# Sheet1.net
KiCad netlist of a schematic drawn in Altium Designer
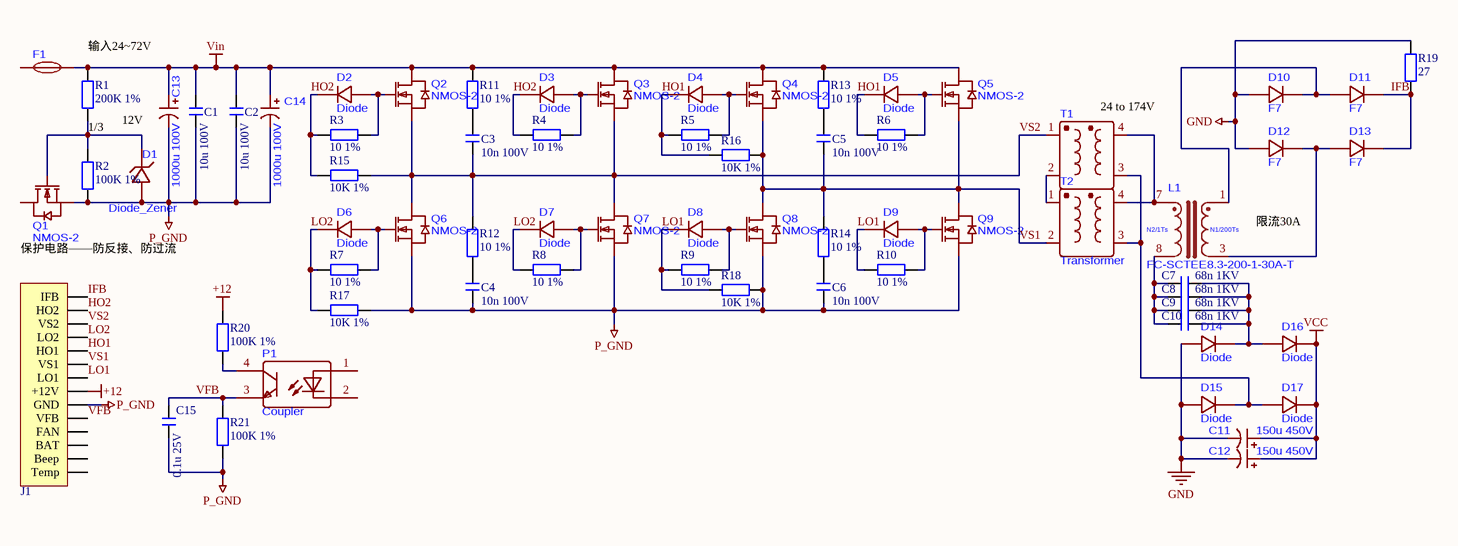
[diagram p0: Sheet1.SchDoc]

(export (version "E")
  (design (tool "Eeschema 10.0.6"))
  (components
    (comp (ref "C1")
      (value "10u 100V")
      (footprint "C2220")
      (description "贴片电容")
      (libsource (lib "自建库") (part "CAP"))
    )
    (comp (ref "C2")
      (value "10u 100V")
      (footprint "C2220")
      (description "贴片电容")
      (libsource (lib "自建库") (part "CAP"))
    )
    (comp (ref "C3")
      (value "10n 100V")
      (footprint "C2220")
      (description "贴片电容")
      (libsource (lib "自建库") (part "CAP"))
    )
    (comp (ref "C4")
      (value "10n 100V")
      (footprint "C2220")
      (description "贴片电容")
      (libsource (lib "自建库") (part "CAP"))
    )
    (comp (ref "C5")
      (value "10n 100V")
      (footprint "C2220")
      (description "贴片电容")
      (libsource (lib "自建库") (part "CAP"))
    )
    (comp (ref "C6")
      (value "10n 100V")
      (footprint "C2220")
      (description "贴片电容")
      (libsource (lib "自建库") (part "CAP"))
    )
    (comp (ref "C7")
      (value "68n 1KV")
      (footprint "CAP-TH_L18.0-W8.5-P15.00-D0.8")
      (description "贴片电容/安规电容")
      (fields (field (name "PART_NUMBER") "MMK683J3ADSAJ208G0"))
      (libsource (lib "自建库") (part "CAP"))
    )
    (comp (ref "C8")
      (value "68n 1KV")
      (footprint "CAP-TH_L18.0-W8.5-P15.00-D0.8")
      (description "贴片电容/安规电容")
      (fields (field (name "PART_NUMBER") "MMK683J3ADSAJ208G0"))
      (libsource (lib "自建库") (part "CAP"))
    )
    (comp (ref "C9")
      (value "68n 1KV")
      (footprint "CAP-TH_L18.0-W8.5-P15.00-D0.8")
      (description "贴片电容/安规电容")
      (fields (field (name "PART_NUMBER") "MMK683J3ADSAJ208G0"))
      (libsource (lib "自建库") (part "CAP"))
    )
    (comp (ref "C10")
      (value "68n 1KV")
      (footprint "CAP-TH_L18.0-W8.5-P15.00-D0.8")
      (description "贴片电容/安规电容")
      (fields (field (name "PART_NUMBER") "MMK683J3ADSAJ208G0"))
      (libsource (lib "自建库") (part "CAP"))
    )
    (comp (ref "C11")
      (value "150u 450V")
      (footprint "CAP-TH_BD22.0-P10.00-D2.3-FD")
      (description "固态电容/电解电容")
      (fields (field (name "PART_NUMBER") "KN151M45022*35A"))
      (libsource (lib "自建库") (part "CAP_1"))
    )
    (comp (ref "C12")
      (value "150u 450V")
      (footprint "CAP-TH_BD22.0-P10.00-D2.3-FD")
      (description "固态电容/电解电容")
      (fields (field (name "PART_NUMBER") "KN151M45022*35A"))
      (libsource (lib "自建库") (part "CAP_1"))
    )
    (comp (ref "C13")
      (value "1000u 100V")
      (footprint "CAP-TH_BD18.0-P7.50-D0.8-FD")
      (description "固态电容/电解电容")
      (fields (field (name "PART_NUMBER") "KF102M10018*36A"))
      (libsource (lib "自建库") (part "CAP_1"))
    )
    (comp (ref "C14")
      (value "1000u 100V")
      (footprint "CAP-TH_BD22.0-P10.00-D2.3-FD")
      (description "固态电容/电解电容")
      (fields (field (name "PART_NUMBER") "KF102M10018*36A"))
      (libsource (lib "自建库") (part "CAP_1"))
    )
    (comp (ref "C15")
      (value "0.1u 25V")
      (footprint "C0805")
      (description "贴片电容/安规电容")
      (fields (field (name "PART_NUMBER") "CC0805MRX7R8BB104"))
      (libsource (lib "自建库") (part "CAP"))
    )
    (comp (ref "D1")
      (value "Diode_Zener")
      (footprint "SOD-123_L2.7-W1.6-LS3.7-RD-1")
      (description "稳压二极管（齐纳二极管），12V,500mW")
      (fields (field (name "PART_NUMBER") "BZT52C12"))
      (libsource (lib "自建库") (part "Diode_Zener"))
    )
    (comp (ref "D2")
      (value "Diode")
      (footprint "SOD-123_L2.7-W1.6-LS3.7-RD-1")
      (description "Diode,1N4148W,开关二极管,CJ(江苏长电/长晶)")
      (fields (field (name "PART_NUMBER") "1N4148W"))
      (libsource (lib "自建库") (part "Diode"))
    )
    (comp (ref "D3")
      (value "Diode")
      (footprint "SOD-123_L2.7-W1.6-LS3.7-RD-1")
      (description "Diode,1N4148W,开关二极管,CJ(江苏长电/长晶)")
      (fields (field (name "PART_NUMBER") "1N4148W"))
      (libsource (lib "自建库") (part "Diode"))
    )
    (comp (ref "D4")
      (value "Diode")
      (footprint "SOD-123_L2.7-W1.6-LS3.7-RD-1")
      (description "Diode,1N4148W,开关二极管,CJ(江苏长电/长晶)")
      (fields (field (name "PART_NUMBER") "1N4148W"))
      (libsource (lib "自建库") (part "Diode"))
    )
    (comp (ref "D5")
      (value "Diode")
      (footprint "SOD-123_L2.7-W1.6-LS3.7-RD-1")
      (description "Diode,1N4148W,开关二极管,CJ(江苏长电/长晶)")
      (fields (field (name "PART_NUMBER") "1N4148W"))
      (libsource (lib "自建库") (part "Diode"))
    )
    (comp (ref "D6")
      (value "Diode")
      (footprint "SOD-123_L2.7-W1.6-LS3.7-RD-1")
      (description "Diode,1N4148W,开关二极管,CJ(江苏长电/长晶)")
      (fields (field (name "PART_NUMBER") "1N4148W"))
      (libsource (lib "自建库") (part "Diode"))
    )
    (comp (ref "D7")
      (value "Diode")
      (footprint "SOD-123_L2.7-W1.6-LS3.7-RD-1")
      (description "Diode,1N4148W,开关二极管,CJ(江苏长电/长晶)")
      (fields (field (name "PART_NUMBER") "1N4148W"))
      (libsource (lib "自建库") (part "Diode"))
    )
    (comp (ref "D8")
      (value "Diode")
      (footprint "SOD-123_L2.7-W1.6-LS3.7-RD-1")
      (description "Diode,1N4148W,开关二极管,CJ(江苏长电/长晶)")
      (fields (field (name "PART_NUMBER") "1N4148W"))
      (libsource (lib "自建库") (part "Diode"))
    )
    (comp (ref "D9")
      (value "Diode")
      (footprint "SOD-123_L2.7-W1.6-LS3.7-RD-1")
      (description "Diode,1N4148W,开关二极管,CJ(江苏长电/长晶)")
      (fields (field (name "PART_NUMBER") "1N4148W"))
      (libsource (lib "自建库") (part "Diode"))
    )
    (comp (ref "D10")
      (value "F7")
      (footprint "DO-214AC_L4.3-W2.7-LS5.2-RD")
      (description "Diode，快恢复/超快恢复二极管，1KV，1A")
      (libsource (lib "自建库") (part "Diode"))
    )
    (comp (ref "D11")
      (value "F7")
      (footprint "DO-214AC_L4.3-W2.7-LS5.2-RD")
      (description "Diode，快恢复/超快恢复二极管，1KV，1A")
      (libsource (lib "自建库") (part "Diode"))
    )
    (comp (ref "D12")
      (value "F7")
      (footprint "DO-214AC_L4.3-W2.7-LS5.2-RD")
      (description "Diode，快恢复/超快恢复二极管，1KV，1A")
      (libsource (lib "自建库") (part "Diode"))
    )
    (comp (ref "D13")
      (value "F7")
      (footprint "DO-214AC_L4.3-W2.7-LS5.2-RD")
      (description "Diode，快恢复/超快恢复二极管，1KV，1A")
      (libsource (lib "自建库") (part "Diode"))
    )
    (comp (ref "D14")
      (value "Diode")
      (footprint "DO-214AC_L4.3-W2.7-LS5.2-RD")
      (fields (field (name "PART_NUMBER") "GC6D10065A"))
      (libsource (lib "自建库") (part "Diode"))
    )
    (comp (ref "D15")
      (value "Diode")
      (footprint "DO-214AC_L4.3-W2.7-LS5.2-RD")
      (fields (field (name "PART_NUMBER") "GC6D10065A"))
      (libsource (lib "自建库") (part "Diode"))
    )
    (comp (ref "D16")
      (value "Diode")
      (footprint "DO-214AC_L4.3-W2.7-LS5.2-RD")
      (fields (field (name "PART_NUMBER") "GC6D10065A"))
      (libsource (lib "自建库") (part "Diode"))
    )
    (comp (ref "D17")
      (value "Diode")
      (footprint "DO-214AC_L4.3-W2.7-LS5.2-RD")
      (fields (field (name "PART_NUMBER") "GC6D10065A"))
      (libsource (lib "自建库") (part "Diode"))
    )
    (comp (ref "F1")
      (value "Fuse-S1032-F-50.0A")
      (footprint "FUSE-SMD_L10.3-W3.2")
      (description "一次性保险丝，额定50A，分断180A")
      (fields (field (name "PART_NUMBER") "S1032-F-50.0A"))
      (libsource (lib "自建库") (part "Fuse-S1032-F-50.0A"))
    )
    (comp (ref "J1")
      (value "HDR-1X14")
      (footprint "HDR2.54-Y-LI-14P")
      (description "Header, 14-Pin")
      (libsource (lib "自建库") (part "EGT003"))
    )
    (comp (ref "L1")
      (value "FC-SCTEE8.3-200-1-30A-T")
      (footprint "XFMR-SMD_FC-SCTEE8.3-200-1-30A-T")
      (description "交流互感器,30A,1:200")
      (libsource (lib "自建库") (part "FC-SCTEE8.3-200-1-30A-T"))
    )
    (comp (ref "P1")
      (value "Coupler")
      (footprint "SOP-4_L6.5-W4.6-P2.54-LS10.2-TL")
      (description "光耦,1.2V,5KV")
      (fields (field (name "PART_NUMBER") "PC817C"))
      (libsource (lib "自建库") (part "Coupler"))
    )
    (comp (ref "Q1")
      (value "NMOS-2")
      (footprint "TO-263-2_L10.2-W8.9-P5.08-LS15.0-BR-1")
      (description "NMOS，100V150A")
      (fields (field (name "PART_NUMBER") "SWB075R08E7T"))
      (libsource (lib "自建库") (part "NMOS-2"))
    )
    (comp (ref "Q2")
      (value "NMOS-2")
      (footprint "TO-247AC-3_L15.8-W5.0-P5.46-L")
      (description "NMOS，150V，171A")
      (fields (field (name "PART_NUMBER") "IRFP4568PBF"))
      (libsource (lib "自建库") (part "NMOS-2"))
    )
    (comp (ref "Q3")
      (value "NMOS-2")
      (footprint "TO-247AC-3_L15.8-W5.0-P5.46-L")
      (description "NMOS，150V，171A")
      (fields (field (name "PART_NUMBER") "IRFP4568PBF"))
      (libsource (lib "自建库") (part "NMOS-2"))
    )
    (comp (ref "Q4")
      (value "NMOS-2")
      (footprint "TO-247AC-3_L15.8-W5.0-P5.46-L")
      (description "NMOS，150V，171A")
      (fields (field (name "PART_NUMBER") "IRFP4568PBF"))
      (libsource (lib "自建库") (part "NMOS-2"))
    )
    (comp (ref "Q5")
      (value "NMOS-2")
      (footprint "TO-247AC-3_L15.8-W5.0-P5.46-L")
      (description "NMOS，150V，171A")
      (fields (field (name "PART_NUMBER") "IRFP4568PBF"))
      (libsource (lib "自建库") (part "NMOS-2"))
    )
    (comp (ref "Q6")
      (value "NMOS-2")
      (footprint "TO-247AC-3_L15.8-W5.0-P5.46-L")
      (description "NMOS，150V，171A")
      (fields (field (name "PART_NUMBER") "IRFP4568PBF"))
      (libsource (lib "自建库") (part "NMOS-2"))
    )
    (comp (ref "Q7")
      (value "NMOS-2")
      (footprint "TO-247AC-3_L15.8-W5.0-P5.46-L")
      (description "NMOS，150V，171A")
      (fields (field (name "PART_NUMBER") "IRFP4568PBF"))
      (libsource (lib "自建库") (part "NMOS-2"))
    )
    (comp (ref "Q8")
      (value "NMOS-2")
      (footprint "TO-247AC-3_L15.8-W5.0-P5.46-L")
      (description "NMOS，150V，171A")
      (fields (field (name "PART_NUMBER") "IRFP4568PBF"))
      (libsource (lib "自建库") (part "NMOS-2"))
    )
    (comp (ref "Q9")
      (value "NMOS-2")
      (footprint "TO-247AC-3_L15.8-W5.0-P5.46-L")
      (description "NMOS，150V，171A")
      (fields (field (name "PART_NUMBER") "IRFP4568PBF"))
      (libsource (lib "自建库") (part "NMOS-2"))
    )
    (comp (ref "R1")
      (value "200K 1%")
      (footprint "R1206")
      (description "贴片电阻")
      (fields (field (name "PART_NUMBER") "AC1206FR-07200KL"))
      (libsource (lib "自建库") (part "RES"))
    )
    (comp (ref "R2")
      (value "100K 1%")
      (footprint "R1206")
      (description "贴片电阻")
      (fields (field (name "PART_NUMBER") "RC1206FR-07100KL"))
      (libsource (lib "自建库") (part "RES"))
    )
    (comp (ref "R3")
      (value "10 1%")
      (footprint "R1206")
      (description "贴片电阻")
      (fields (field (name "PART_NUMBER") "RC1206FR-0710RL"))
      (libsource (lib "自建库") (part "RES"))
    )
    (comp (ref "R4")
      (value "10 1%")
      (footprint "R1206")
      (description "贴片电阻")
      (fields (field (name "PART_NUMBER") "RC1206FR-0710RL"))
      (libsource (lib "自建库") (part "RES"))
    )
    (comp (ref "R5")
      (value "10 1%")
      (footprint "R1206")
      (description "贴片电阻")
      (fields (field (name "PART_NUMBER") "RC1206FR-0710RL"))
      (libsource (lib "自建库") (part "RES"))
    )
    (comp (ref "R6")
      (value "10 1%")
      (footprint "R1206")
      (description "贴片电阻")
      (fields (field (name "PART_NUMBER") "RC1206FR-0710RL"))
      (libsource (lib "自建库") (part "RES"))
    )
    (comp (ref "R7")
      (value "10 1%")
      (footprint "R1206")
      (description "贴片电阻")
      (fields (field (name "PART_NUMBER") "RC1206FR-0710RL"))
      (libsource (lib "自建库") (part "RES"))
    )
    (comp (ref "R8")
      (value "10 1%")
      (footprint "R1206")
      (description "贴片电阻")
      (fields (field (name "PART_NUMBER") "RC1206FR-0710RL"))
      (libsource (lib "自建库") (part "RES"))
    )
    (comp (ref "R9")
      (value "10 1%")
      (footprint "R1206")
      (description "贴片电阻")
      (fields (field (name "PART_NUMBER") "RC1206FR-0710RL"))
      (libsource (lib "自建库") (part "RES"))
    )
    (comp (ref "R10")
      (value "10 1%")
      (footprint "R1206")
      (description "贴片电阻")
      (fields (field (name "PART_NUMBER") "RC1206FR-0710RL"))
      (libsource (lib "自建库") (part "RES"))
    )
    (comp (ref "R11")
      (value "10 1%")
      (footprint "R1206")
      (description "贴片电阻")
      (fields (field (name "PART_NUMBER") "RC1206FR-0710RL"))
      (libsource (lib "自建库") (part "RES"))
    )
    (comp (ref "R12")
      (value "10 1%")
      (footprint "R1206")
      (description "贴片电阻")
      (fields (field (name "PART_NUMBER") "RC1206FR-0710RL"))
      (libsource (lib "自建库") (part "RES"))
    )
    (comp (ref "R13")
      (value "10 1%")
      (footprint "R1206")
      (description "贴片电阻")
      (fields (field (name "PART_NUMBER") "RC1206FR-0710RL"))
      (libsource (lib "自建库") (part "RES"))
    )
    (comp (ref "R14")
      (value "10 1%")
      (footprint "R1206")
      (description "贴片电阻")
      (fields (field (name "PART_NUMBER") "RC1206FR-0710RL"))
      (libsource (lib "自建库") (part "RES"))
    )
    (comp (ref "R15")
      (value "10K 1%")
      (footprint "R1206")
      (description "贴片电阻")
      (fields (field (name "PART_NUMBER") "RC1206FR-0710KL"))
      (libsource (lib "自建库") (part "RES"))
    )
    (comp (ref "R16")
      (value "10K 1%")
      (footprint "R1206")
      (description "贴片电阻")
      (fields (field (name "PART_NUMBER") "RC1206FR-0710KL"))
      (libsource (lib "自建库") (part "RES"))
    )
    (comp (ref "R17")
      (value "10K 1%")
      (footprint "R1206")
      (description "贴片电阻")
      (fields (field (name "PART_NUMBER") "RC1206FR-0710KL"))
      (libsource (lib "自建库") (part "RES"))
    )
    (comp (ref "R18")
      (value "10K 1%")
      (footprint "R1206")
      (description "贴片电阻")
      (fields (field (name "PART_NUMBER") "RC1206FR-0710KL"))
      (libsource (lib "自建库") (part "RES"))
    )
    (comp (ref "R19")
      (value "27")
      (footprint "R1206")
      (description "贴片电阻")
      (fields (field (name "PART_NUMBER") "RC1206FR-0727RL"))
      (libsource (lib "自建库") (part "RES"))
    )
    (comp (ref "R20")
      (value "100K 1%")
      (footprint "R1206")
      (description "贴片电阻")
      (libsource (lib "自建库") (part "RES"))
    )
    (comp (ref "R21")
      (value "100K 1%")
      (footprint "R1206")
      (description "贴片电阻")
      (libsource (lib "自建库") (part "RES"))
    )
    (comp (ref "T1")
      (value "Transformer")
      (footprint "TAN-PQ5035(4+6) -4")
      (description "变压器,2KW,29:4,屹晶微定制")
      (libsource (lib "自建库") (part "Transformer"))
    )
    (comp (ref "T2")
      (value "Transformer")
      (footprint "TAN-PQ5035(4+6) -4")
      (description "变压器,2KW,29:4,屹晶微定制")
      (libsource (lib "自建库") (part "Transformer"))
    )
  )
  (nets
    (net (code "1") (name "+12") (class "Default")
      (node (ref "J1") (pin "7") (pinfunction "+12V_7") (pintype "passive"))
      (node (ref "R20") (pin "2") (pinfunction "2_2") (pintype "passive"))
    )
    (net (code "2") (name "/HO1") (class "Default")
      (node (ref "D4") (pin "1") (pinfunction "-_1") (pintype "passive"))
      (node (ref "D5") (pin "1") (pinfunction "-_1") (pintype "passive"))
      (node (ref "J1") (pin "10") (pinfunction "HO1_10") (pintype "passive"))
      (node (ref "R16") (pin "1") (pinfunction "1_1") (pintype "passive"))
      (node (ref "R5") (pin "1") (pinfunction "1_1") (pintype "passive"))
      (node (ref "R6") (pin "1") (pinfunction "1_1") (pintype "passive"))
    )
    (net (code "3") (name "/HO2") (class "Default")
      (node (ref "D2") (pin "1") (pinfunction "-_1") (pintype "passive"))
      (node (ref "D3") (pin "1") (pinfunction "-_1") (pintype "passive"))
      (node (ref "J1") (pin "13") (pinfunction "HO2_13") (pintype "passive"))
      (node (ref "R15") (pin "1") (pinfunction "1_1") (pintype "passive"))
      (node (ref "R3") (pin "1") (pinfunction "1_1") (pintype "passive"))
      (node (ref "R4") (pin "1") (pinfunction "1_1") (pintype "passive"))
    )
    (net (code "4") (name "/IFB") (class "Default")
      (node (ref "D11") (pin "1") (pinfunction "-_1") (pintype "passive"))
      (node (ref "D13") (pin "1") (pinfunction "-_1") (pintype "passive"))
      (node (ref "J1") (pin "14") (pinfunction "IFB_14") (pintype "passive"))
      (node (ref "R19") (pin "2") (pinfunction "2_2") (pintype "passive"))
    )
    (net (code "5") (name "/LO1") (class "Default")
      (node (ref "D8") (pin "1") (pinfunction "-_1") (pintype "passive"))
      (node (ref "D9") (pin "1") (pinfunction "-_1") (pintype "passive"))
      (node (ref "J1") (pin "8") (pinfunction "LO1_8") (pintype "passive"))
      (node (ref "R10") (pin "1") (pinfunction "1_1") (pintype "passive"))
      (node (ref "R18") (pin "1") (pinfunction "1_1") (pintype "passive"))
      (node (ref "R9") (pin "1") (pinfunction "1_1") (pintype "passive"))
    )
    (net (code "6") (name "/LO2") (class "Default")
      (node (ref "D6") (pin "1") (pinfunction "-_1") (pintype "passive"))
      (node (ref "D7") (pin "1") (pinfunction "-_1") (pintype "passive"))
      (node (ref "J1") (pin "11") (pinfunction "LO2_11") (pintype "passive"))
      (node (ref "R17") (pin "1") (pinfunction "1_1") (pintype "passive"))
      (node (ref "R7") (pin "1") (pinfunction "1_1") (pintype "passive"))
      (node (ref "R8") (pin "1") (pinfunction "1_1") (pintype "passive"))
    )
    (net (code "7") (name "/VFB") (class "Default")
      (node (ref "C15") (pin "2") (pinfunction "2_2") (pintype "passive"))
      (node (ref "J1") (pin "5") (pinfunction "VFB_5") (pintype "passive"))
      (node (ref "P1") (pin "3") (pinfunction "3_3") (pintype "passive"))
      (node (ref "R21") (pin "2") (pinfunction "2_2") (pintype "passive"))
    )
    (net (code "8") (name "/VS1") (class "Default")
      (node (ref "C5") (pin "2") (pinfunction "2_2") (pintype "passive"))
      (node (ref "J1") (pin "9") (pinfunction "VS1_9") (pintype "passive"))
      (node (ref "Q4") (pin "2") (pinfunction "S_2") (pintype "passive"))
      (node (ref "Q5") (pin "2") (pinfunction "S_2") (pintype "passive"))
      (node (ref "Q8") (pin "3") (pinfunction "D_3") (pintype "passive"))
      (node (ref "Q9") (pin "3") (pinfunction "D_3") (pintype "passive"))
      (node (ref "R14") (pin "1") (pinfunction "1_1") (pintype "passive"))
      (node (ref "R16") (pin "2") (pinfunction "2_2") (pintype "passive"))
      (node (ref "T2") (pin "2") (pinfunction "2_2") (pintype "passive"))
    )
    (net (code "9") (name "/VS2") (class "Default")
      (node (ref "C3") (pin "1") (pinfunction "1_1") (pintype "passive"))
      (node (ref "J1") (pin "12") (pinfunction "VS2_12") (pintype "passive"))
      (node (ref "Q2") (pin "2") (pinfunction "S_2") (pintype "passive"))
      (node (ref "Q3") (pin "2") (pinfunction "S_2") (pintype "passive"))
      (node (ref "Q6") (pin "3") (pinfunction "D_3") (pintype "passive"))
      (node (ref "Q7") (pin "3") (pinfunction "D_3") (pintype "passive"))
      (node (ref "R12") (pin "1") (pinfunction "1_1") (pintype "passive"))
      (node (ref "R15") (pin "2") (pinfunction "2_2") (pintype "passive"))
      (node (ref "T1") (pin "1") (pinfunction "1_1") (pintype "passive"))
    )
    (net (code "10") (name "GND") (class "Default")
      (node (ref "C11") (pin "2") (pinfunction "2_2") (pintype "passive"))
      (node (ref "C12") (pin "2") (pinfunction "2_2") (pintype "passive"))
      (node (ref "D10") (pin "2") (pinfunction "+_2") (pintype "passive"))
      (node (ref "D12") (pin "2") (pinfunction "+_2") (pintype "passive"))
      (node (ref "D14") (pin "2") (pinfunction "+_2") (pintype "passive"))
      (node (ref "D15") (pin "2") (pinfunction "+_2") (pintype "passive"))
      (node (ref "R19") (pin "1") (pinfunction "1_1") (pintype "passive"))
    )
    (net (code "11") (name "Net-(C3-Pad2)") (class "Default")
      (node (ref "C3") (pin "2") (pinfunction "2_2") (pintype "passive"))
      (node (ref "R11") (pin "1") (pinfunction "1_1") (pintype "passive"))
    )
    (net (code "12") (name "Net-(C4-Pad1)") (class "Default")
      (node (ref "C4") (pin "1") (pinfunction "1_1") (pintype "passive"))
      (node (ref "R12") (pin "2") (pinfunction "2_2") (pintype "passive"))
    )
    (net (code "13") (name "Net-(C5-Pad1)") (class "Default")
      (node (ref "C5") (pin "1") (pinfunction "1_1") (pintype "passive"))
      (node (ref "R13") (pin "2") (pinfunction "2_2") (pintype "passive"))
    )
    (net (code "14") (name "Net-(C6-Pad1)") (class "Default")
      (node (ref "C6") (pin "1") (pinfunction "1_1") (pintype "passive"))
      (node (ref "R14") (pin "2") (pinfunction "2_2") (pintype "passive"))
    )
    (net (code "15") (name "Net-(C10-Pad1)") (class "Default")
      (node (ref "C10") (pin "1") (pinfunction "1_1") (pintype "passive"))
      (node (ref "C7") (pin "1") (pinfunction "1_1") (pintype "passive"))
      (node (ref "C8") (pin "1") (pinfunction "1_1") (pintype "passive"))
      (node (ref "C9") (pin "1") (pinfunction "1_1") (pintype "passive"))
      (node (ref "L1") (pin "8") (pinfunction "8_8") (pintype "passive"))
    )
    (net (code "16") (name "Net-(D1-K)") (class "Default")
      (node (ref "D1") (pin "1") (pinfunction "K_1") (pintype "passive"))
      (node (ref "Q1") (pin "1") (pinfunction "G_1") (pintype "passive"))
      (node (ref "R1") (pin "1") (pinfunction "1_1") (pintype "passive"))
      (node (ref "R2") (pin "2") (pinfunction "2_2") (pintype "passive"))
    )
    (net (code "17") (name "Net-(D2-+)") (class "Default")
      (node (ref "D2") (pin "2") (pinfunction "+_2") (pintype "passive"))
      (node (ref "Q2") (pin "1") (pinfunction "G_1") (pintype "passive"))
      (node (ref "R3") (pin "2") (pinfunction "2_2") (pintype "passive"))
    )
    (net (code "18") (name "Net-(D3-+)") (class "Default")
      (node (ref "D3") (pin "2") (pinfunction "+_2") (pintype "passive"))
      (node (ref "Q3") (pin "1") (pinfunction "G_1") (pintype "passive"))
      (node (ref "R4") (pin "2") (pinfunction "2_2") (pintype "passive"))
    )
    (net (code "19") (name "Net-(D4-+)") (class "Default")
      (node (ref "D4") (pin "2") (pinfunction "+_2") (pintype "passive"))
      (node (ref "Q4") (pin "1") (pinfunction "G_1") (pintype "passive"))
      (node (ref "R5") (pin "2") (pinfunction "2_2") (pintype "passive"))
    )
    (net (code "20") (name "Net-(D5-+)") (class "Default")
      (node (ref "D5") (pin "2") (pinfunction "+_2") (pintype "passive"))
      (node (ref "Q5") (pin "1") (pinfunction "G_1") (pintype "passive"))
      (node (ref "R6") (pin "2") (pinfunction "2_2") (pintype "passive"))
    )
    (net (code "21") (name "Net-(D6-+)") (class "Default")
      (node (ref "D6") (pin "2") (pinfunction "+_2") (pintype "passive"))
      (node (ref "Q6") (pin "1") (pinfunction "G_1") (pintype "passive"))
      (node (ref "R7") (pin "2") (pinfunction "2_2") (pintype "passive"))
    )
    (net (code "22") (name "Net-(D7-+)") (class "Default")
      (node (ref "D7") (pin "2") (pinfunction "+_2") (pintype "passive"))
      (node (ref "Q7") (pin "1") (pinfunction "G_1") (pintype "passive"))
      (node (ref "R8") (pin "2") (pinfunction "2_2") (pintype "passive"))
    )
    (net (code "23") (name "Net-(D8-+)") (class "Default")
      (node (ref "D8") (pin "2") (pinfunction "+_2") (pintype "passive"))
      (node (ref "Q8") (pin "1") (pinfunction "G_1") (pintype "passive"))
      (node (ref "R9") (pin "2") (pinfunction "2_2") (pintype "passive"))
    )
    (net (code "24") (name "Net-(D9-+)") (class "Default")
      (node (ref "D9") (pin "2") (pinfunction "+_2") (pintype "passive"))
      (node (ref "Q9") (pin "1") (pinfunction "G_1") (pintype "passive"))
      (node (ref "R10") (pin "2") (pinfunction "2_2") (pintype "passive"))
    )
    (net (code "25") (name "Net-(D10--)") (class "Default")
      (node (ref "D10") (pin "1") (pinfunction "-_1") (pintype "passive"))
      (node (ref "D11") (pin "2") (pinfunction "+_2") (pintype "passive"))
      (node (ref "L1") (pin "1") (pinfunction "1_1") (pintype "passive"))
    )
    (net (code "26") (name "Net-(D12--)") (class "Default")
      (node (ref "D12") (pin "1") (pinfunction "-_1") (pintype "passive"))
      (node (ref "D13") (pin "2") (pinfunction "+_2") (pintype "passive"))
      (node (ref "L1") (pin "3") (pinfunction "3_3") (pintype "passive"))
    )
    (net (code "27") (name "Net-(D14--)") (class "Default")
      (node (ref "C10") (pin "2") (pinfunction "2_2") (pintype "passive"))
      (node (ref "C7") (pin "2") (pinfunction "2_2") (pintype "passive"))
      (node (ref "C8") (pin "2") (pinfunction "2_2") (pintype "passive"))
      (node (ref "C9") (pin "2") (pinfunction "2_2") (pintype "passive"))
      (node (ref "D14") (pin "1") (pinfunction "-_1") (pintype "passive"))
      (node (ref "D16") (pin "2") (pinfunction "+_2") (pintype "passive"))
    )
    (net (code "28") (name "Net-(D15--)") (class "Default")
      (node (ref "D15") (pin "1") (pinfunction "-_1") (pintype "passive"))
      (node (ref "D17") (pin "2") (pinfunction "+_2") (pintype "passive"))
      (node (ref "T1") (pin "3") (pinfunction "3_3") (pintype "passive"))
      (node (ref "T2") (pin "3") (pinfunction "3_3") (pintype "passive"))
    )
    (net (code "29") (name "Net-(L1-Pad7)") (class "Default")
      (node (ref "L1") (pin "7") (pinfunction "7_7") (pintype "passive"))
      (node (ref "T1") (pin "4") (pinfunction "4_4") (pintype "passive"))
      (node (ref "T2") (pin "4") (pinfunction "4_4") (pintype "passive"))
    )
    (net (code "30") (name "Net-(P1-Pad4)") (class "Default")
      (node (ref "P1") (pin "4") (pinfunction "4_4") (pintype "passive"))
      (node (ref "R20") (pin "1") (pinfunction "1_1") (pintype "passive"))
    )
    (net (code "31") (name "Net-(T1-Pad2)") (class "Default")
      (node (ref "T1") (pin "2") (pinfunction "2_2") (pintype "passive"))
      (node (ref "T2") (pin "1") (pinfunction "1_1") (pintype "passive"))
    )
    (net (code "32") (name "P_GND") (class "Default")
      (node (ref "C1") (pin "2") (pinfunction "2_2") (pintype "passive"))
      (node (ref "C13") (pin "2") (pinfunction "2_2") (pintype "passive"))
      (node (ref "C14") (pin "2") (pinfunction "2_2") (pintype "passive"))
      (node (ref "C15") (pin "1") (pinfunction "1_1") (pintype "passive"))
      (node (ref "C2") (pin "2") (pinfunction "2_2") (pintype "passive"))
      (node (ref "C4") (pin "2") (pinfunction "2_2") (pintype "passive"))
      (node (ref "C6") (pin "2") (pinfunction "2_2") (pintype "passive"))
      (node (ref "D1") (pin "2") (pinfunction "A_2") (pintype "passive"))
      (node (ref "J1") (pin "6") (pinfunction "GND_6") (pintype "passive"))
      (node (ref "Q1") (pin "2") (pinfunction "S_2") (pintype "passive"))
      (node (ref "Q6") (pin "2") (pinfunction "S_2") (pintype "passive"))
      (node (ref "Q7") (pin "2") (pinfunction "S_2") (pintype "passive"))
      (node (ref "Q8") (pin "2") (pinfunction "S_2") (pintype "passive"))
      (node (ref "Q9") (pin "2") (pinfunction "S_2") (pintype "passive"))
      (node (ref "R17") (pin "2") (pinfunction "2_2") (pintype "passive"))
      (node (ref "R18") (pin "2") (pinfunction "2_2") (pintype "passive"))
      (node (ref "R2") (pin "1") (pinfunction "1_1") (pintype "passive"))
      (node (ref "R21") (pin "1") (pinfunction "1_1") (pintype "passive"))
    )
    (net (code "33") (name "VCC") (class "Default")
      (node (ref "C11") (pin "1") (pinfunction "1_1") (pintype "passive"))
      (node (ref "C12") (pin "1") (pinfunction "1_1") (pintype "passive"))
      (node (ref "D16") (pin "1") (pinfunction "-_1") (pintype "passive"))
      (node (ref "D17") (pin "1") (pinfunction "-_1") (pintype "passive"))
    )
    (net (code "34") (name "Vin") (class "Default")
      (node (ref "C1") (pin "1") (pinfunction "1_1") (pintype "passive"))
      (node (ref "C13") (pin "1") (pinfunction "1_1") (pintype "passive"))
      (node (ref "C14") (pin "1") (pinfunction "1_1") (pintype "passive"))
      (node (ref "C2") (pin "1") (pinfunction "1_1") (pintype "passive"))
      (node (ref "F1") (pin "2") (pinfunction "2_2") (pintype "passive"))
      (node (ref "Q2") (pin "3") (pinfunction "D_3") (pintype "passive"))
      (node (ref "Q3") (pin "3") (pinfunction "D_3") (pintype "passive"))
      (node (ref "Q4") (pin "3") (pinfunction "D_3") (pintype "passive"))
      (node (ref "Q5") (pin "3") (pinfunction "D_3") (pintype "passive"))
      (node (ref "R1") (pin "2") (pinfunction "2_2") (pintype "passive"))
      (node (ref "R11") (pin "2") (pinfunction "2_2") (pintype "passive"))
      (node (ref "R13") (pin "1") (pinfunction "1_1") (pintype "passive"))
    )
    (net (code "35") (name "unconnected-(F1-Pad1)") (class "Default")
      (node (ref "F1") (pin "1") (pinfunction "1_1") (pintype "passive"))
    )
    (net (code "36") (name "unconnected-(J1-BAT-Pad3)") (class "Default")
      (node (ref "J1") (pin "3") (pinfunction "BAT_3") (pintype "passive"))
    )
    (net (code "37") (name "unconnected-(J1-Beep-Pad2)") (class "Default")
      (node (ref "J1") (pin "2") (pinfunction "Beep_2") (pintype "passive"))
    )
    (net (code "38") (name "unconnected-(J1-FAN-Pad4)") (class "Default")
      (node (ref "J1") (pin "4") (pinfunction "FAN_4") (pintype "passive"))
    )
    (net (code "39") (name "unconnected-(J1-Temp-Pad1)") (class "Default")
      (node (ref "J1") (pin "1") (pinfunction "Temp_1") (pintype "passive"))
    )
    (net (code "40") (name "unconnected-(P1-Pad1)") (class "Default")
      (node (ref "P1") (pin "1") (pinfunction "1_1") (pintype "passive"))
    )
    (net (code "41") (name "unconnected-(P1-Pad2)") (class "Default")
      (node (ref "P1") (pin "2") (pinfunction "2_2") (pintype "passive"))
    )
    (net (code "42") (name "unconnected-(Q1-D-Pad3)") (class "Default")
      (node (ref "Q1") (pin "3") (pinfunction "D_3") (pintype "passive"))
    )
  )
)
